# wm8731adapter.net
KiCad netlist of a schematic drawn in EAGLE
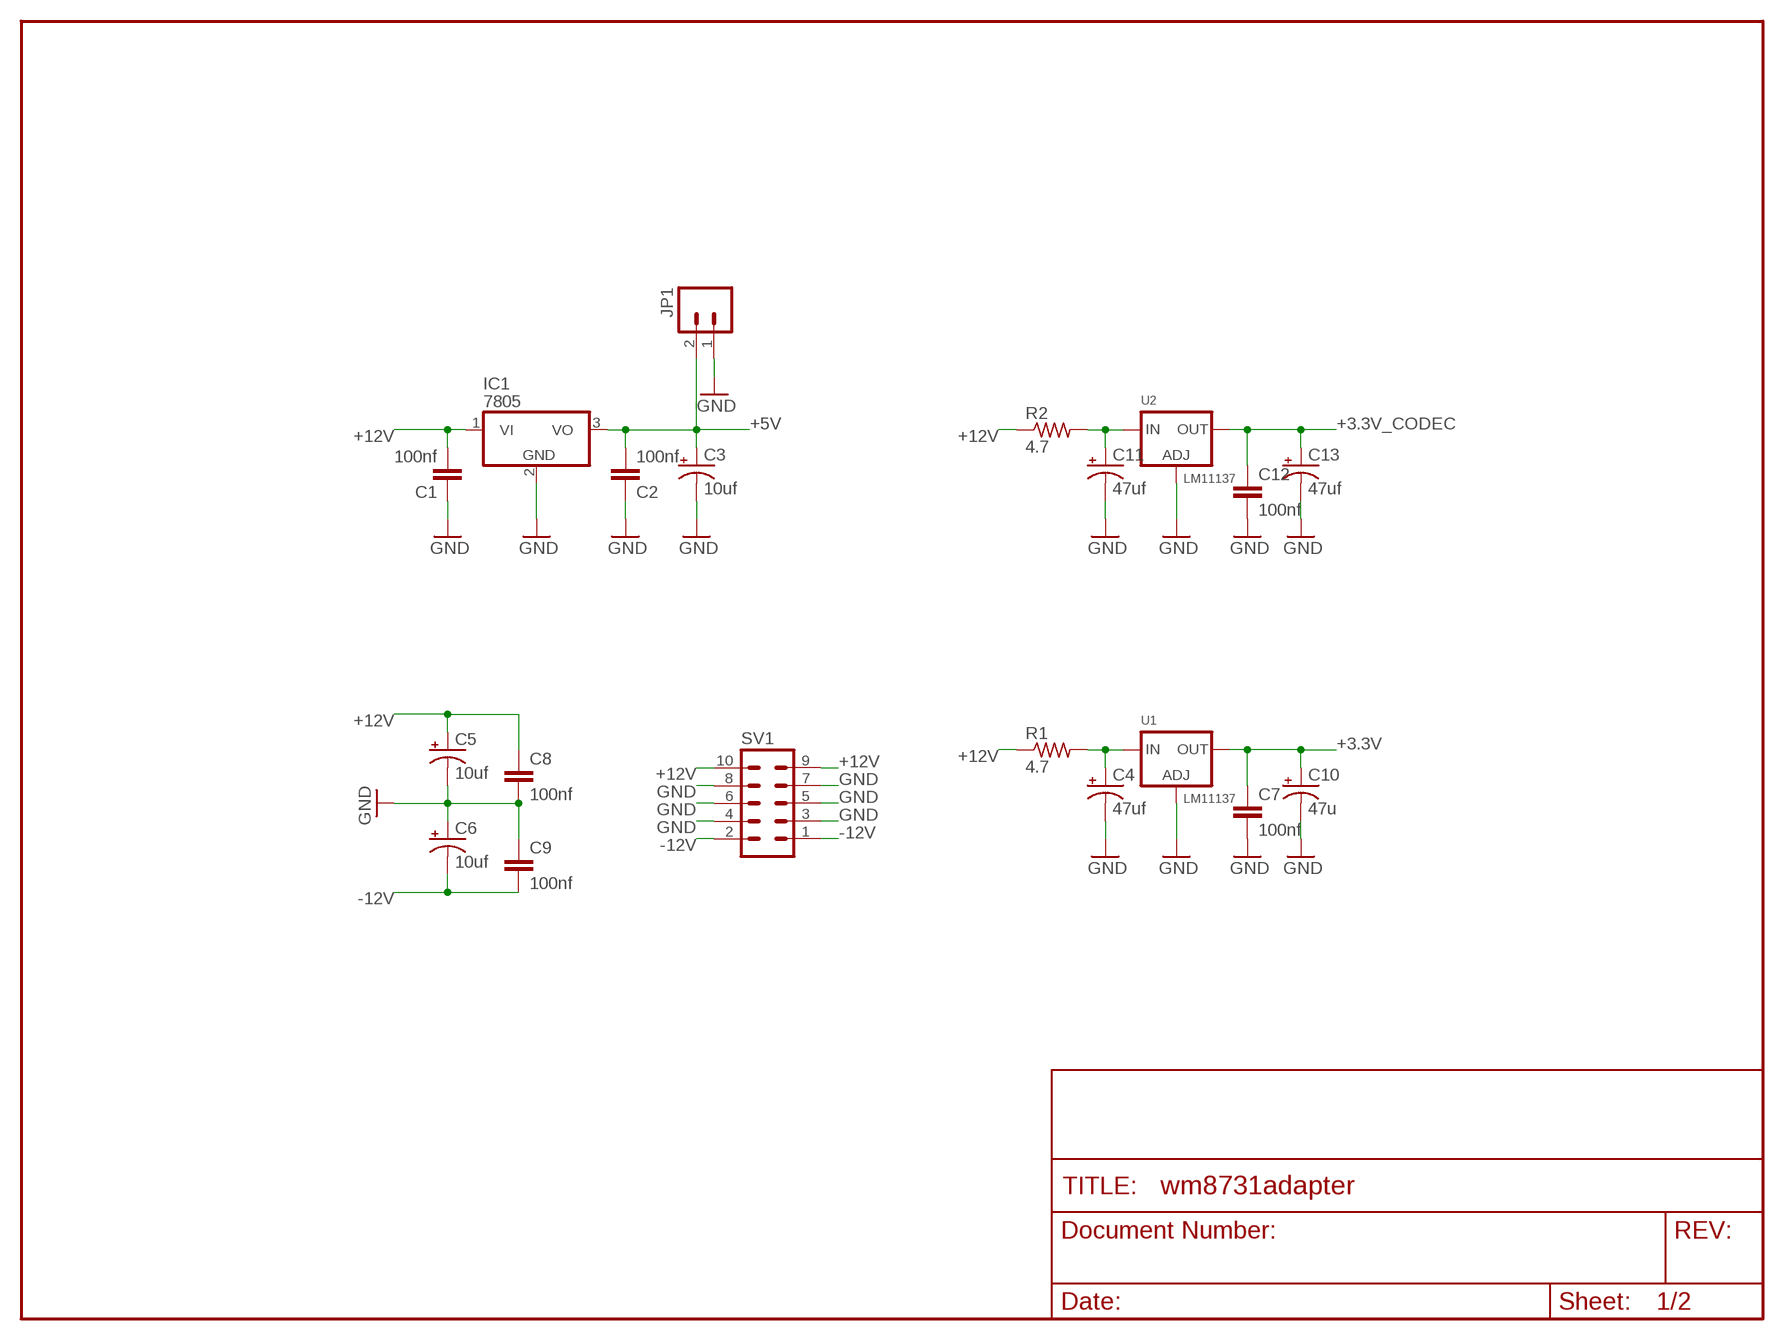
[diagram p0: schematic, sheet 1]
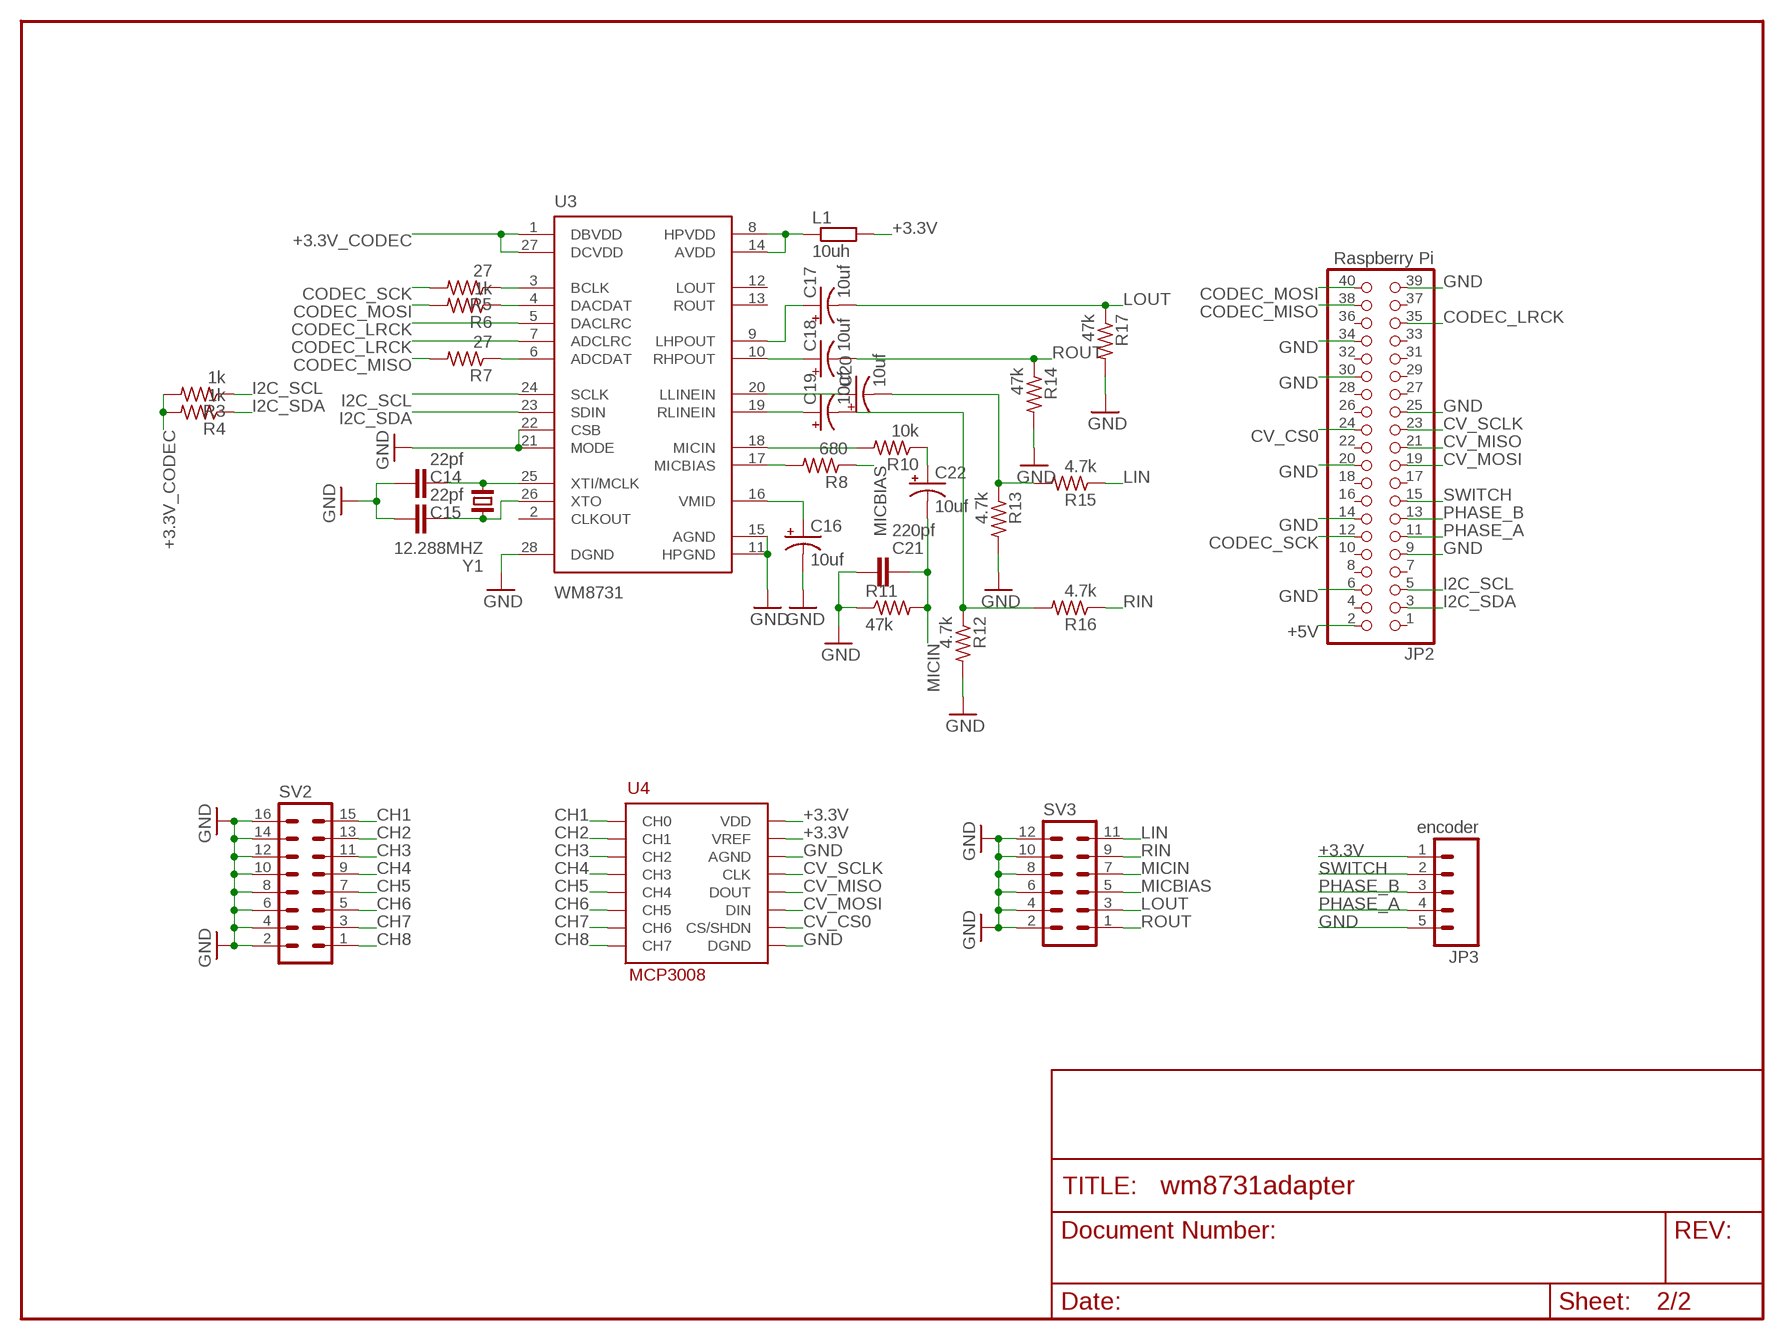
[diagram p1: schematic, sheet 2]

(export (version "E")
  (design (tool "Eeschema 10.0.6"))
  (components
    (comp (ref "C1")
      (value "100nf")
      (footprint "eagle-import:C0603")
      (libsource (lib "eagle-import") (part "C-EUC0603"))
    )
    (comp (ref "C2")
      (value "100nf")
      (footprint "eagle-import:C0603")
      (libsource (lib "eagle-import") (part "C-EUC0603"))
    )
    (comp (ref "C3")
      (value "10uf")
      (footprint "eagle-import:PANASONIC_C")
      (libsource (lib "eagle-import") (part "CPOL-USC"))
    )
    (comp (ref "C4")
      (value "47uf")
      (footprint "eagle-import:PANASONIC_D")
      (libsource (lib "eagle-import") (part "CPOL-USD"))
    )
    (comp (ref "C5")
      (value "10uf")
      (footprint "eagle-import:PANASONIC_C")
      (libsource (lib "eagle-import") (part "CPOL-USC"))
    )
    (comp (ref "C6")
      (value "10uf")
      (footprint "eagle-import:PANASONIC_C")
      (libsource (lib "eagle-import") (part "CPOL-USC"))
    )
    (comp (ref "C7")
      (value "100nf")
      (footprint "eagle-import:C0603")
      (libsource (lib "eagle-import") (part "C-EUC0603"))
    )
    (comp (ref "C8")
      (value "100nf")
      (footprint "eagle-import:C0603")
      (libsource (lib "eagle-import") (part "C-EUC0603"))
    )
    (comp (ref "C9")
      (value "100nf")
      (footprint "eagle-import:C0603")
      (libsource (lib "eagle-import") (part "C-EUC0603"))
    )
    (comp (ref "C10")
      (value "47u")
      (footprint "eagle-import:PANASONIC_D")
      (libsource (lib "eagle-import") (part "CPOL-USD"))
    )
    (comp (ref "C11")
      (value "47uf")
      (footprint "eagle-import:PANASONIC_D")
      (libsource (lib "eagle-import") (part "CPOL-USD"))
    )
    (comp (ref "C12")
      (value "100nf")
      (footprint "eagle-import:C0603")
      (libsource (lib "eagle-import") (part "C-EUC0603"))
    )
    (comp (ref "C13")
      (value "47uf")
      (footprint "eagle-import:PANASONIC_D")
      (libsource (lib "eagle-import") (part "CPOL-USD"))
    )
    (comp (ref "IC1")
      (value "7805")
      (footprint "eagle-import:TO220V")
      (libsource (lib "eagle-import") (part "78TV05"))
    )
    (comp (ref "JP1")
      (value "M02_HEADERPOLAR")
      (footprint "eagle-import:MOLEX-1X2")
      (libsource (lib "eagle-import") (part "M02_HEADERPOLAR"))
    )
    (comp (ref "R1")
      (value "4.7")
      (footprint "eagle-import:R1206")
      (libsource (lib "eagle-import") (part "R-US_R1206"))
    )
    (comp (ref "R2")
      (value "4.7")
      (footprint "eagle-import:R1206")
      (libsource (lib "eagle-import") (part "R-US_R1206"))
    )
    (comp (ref "SV1")
      (value "MA05-2")
      (footprint "eagle-import:MA05-2")
      (libsource (lib "eagle-import") (part "MA05-2"))
    )
    (comp (ref "U1")
      (value "LM11137")
      (footprint "eagle-import:TO252")
      (libsource (lib "eagle-import") (part "LM1117TO252"))
    )
    (comp (ref "U2")
      (value "LM11137")
      (footprint "eagle-import:SOT223-R")
      (libsource (lib "eagle-import") (part "LM1117SOT223-REFLOW"))
    )
    (comp (ref "C14")
      (value "22pf")
      (footprint "eagle-import:C0603")
      (libsource (lib "eagle-import") (part "C-EUC0603"))
    )
    (comp (ref "C15")
      (value "22pf")
      (footprint "eagle-import:C0603")
      (libsource (lib "eagle-import") (part "C-EUC0603"))
    )
    (comp (ref "C16")
      (value "10uf")
      (footprint "eagle-import:PANASONIC_C")
      (libsource (lib "eagle-import") (part "CPOL-USC"))
    )
    (comp (ref "C17")
      (value "10uf")
      (footprint "eagle-import:PANASONIC_C")
      (libsource (lib "eagle-import") (part "CPOL-USC"))
    )
    (comp (ref "C18")
      (value "10uf")
      (footprint "eagle-import:PANASONIC_C")
      (libsource (lib "eagle-import") (part "CPOL-USC"))
    )
    (comp (ref "C19")
      (value "10uf")
      (footprint "eagle-import:PANASONIC_C")
      (libsource (lib "eagle-import") (part "CPOL-USC"))
    )
    (comp (ref "C20")
      (value "10uf")
      (footprint "eagle-import:PANASONIC_C")
      (libsource (lib "eagle-import") (part "CPOL-USC"))
    )
    (comp (ref "C21")
      (value "220pf")
      (footprint "eagle-import:C0603")
      (libsource (lib "eagle-import") (part "C-EUC0603"))
    )
    (comp (ref "C22")
      (value "10uf")
      (footprint "eagle-import:PANASONIC_C")
      (libsource (lib "eagle-import") (part "CPOL-USC"))
    )
    (comp (ref "JP2")
      (value "Raspberry Pi")
      (footprint "eagle-import:2X20")
      (libsource (lib "eagle-import") (part "PINHD-2X20"))
    )
    (comp (ref "JP3")
      (value "encoder")
      (footprint "eagle-import:1X05")
      (libsource (lib "eagle-import") (part "M05PTH"))
    )
    (comp (ref "L1")
      (value "10uh")
      (footprint "eagle-import:1_4W_RESISTOR")
      (libsource (lib "eagle-import") (part "RESISTOR10MM"))
    )
    (comp (ref "R3")
      (value "1k")
      (footprint "eagle-import:R0603")
      (libsource (lib "eagle-import") (part "R-US_R0603"))
    )
    (comp (ref "R4")
      (value "1k")
      (footprint "eagle-import:R0603")
      (libsource (lib "eagle-import") (part "R-US_R0603"))
    )
    (comp (ref "R5")
      (value "27")
      (footprint "eagle-import:R0603")
      (libsource (lib "eagle-import") (part "R-US_R0603"))
    )
    (comp (ref "R6")
      (value "1k")
      (footprint "eagle-import:R0603")
      (libsource (lib "eagle-import") (part "R-US_R0603"))
    )
    (comp (ref "R7")
      (value "27")
      (footprint "eagle-import:R0603")
      (libsource (lib "eagle-import") (part "R-US_R0603"))
    )
    (comp (ref "R8")
      (value "680")
      (footprint "eagle-import:R0603")
      (libsource (lib "eagle-import") (part "R-US_R0603"))
    )
    (comp (ref "R10")
      (value "10k")
      (footprint "eagle-import:R0603")
      (libsource (lib "eagle-import") (part "R-US_R0603"))
    )
    (comp (ref "R11")
      (value "47k")
      (footprint "eagle-import:R0603")
      (libsource (lib "eagle-import") (part "R-US_R0603"))
    )
    (comp (ref "R12")
      (value "4.7k")
      (footprint "eagle-import:R0603")
      (libsource (lib "eagle-import") (part "R-US_R0603"))
    )
    (comp (ref "R13")
      (value "4.7k")
      (footprint "eagle-import:R0603")
      (libsource (lib "eagle-import") (part "R-US_R0603"))
    )
    (comp (ref "R14")
      (value "47k")
      (footprint "eagle-import:R0603")
      (libsource (lib "eagle-import") (part "R-US_R0603"))
    )
    (comp (ref "R15")
      (value "4.7k")
      (footprint "eagle-import:R0603")
      (libsource (lib "eagle-import") (part "R-US_R0603"))
    )
    (comp (ref "R16")
      (value "4.7k")
      (footprint "eagle-import:R0603")
      (libsource (lib "eagle-import") (part "R-US_R0603"))
    )
    (comp (ref "R17")
      (value "47k")
      (footprint "eagle-import:R0603")
      (libsource (lib "eagle-import") (part "R-US_R0603"))
    )
    (comp (ref "SV2")
      (value "MA08-2")
      (footprint "eagle-import:MA08-2")
      (libsource (lib "eagle-import") (part "MA08-2"))
    )
    (comp (ref "SV3")
      (value "MA06-2")
      (footprint "eagle-import:MA06-2")
      (libsource (lib "eagle-import") (part "MA06-2"))
    )
    (comp (ref "U3")
      (value "WM8731")
      (footprint "eagle-import:SSOP28")
      (libsource (lib "eagle-import") (part "WM8731"))
    )
    (comp (ref "U4")
      (value "MCP3008")
      (footprint "eagle-import:SOIC16")
      (libsource (lib "eagle-import") (part "MCP3008"))
    )
    (comp (ref "Y1")
      (value "12.288MHZ")
      (footprint "eagle-import:HC49UP")
      (libsource (lib "eagle-import") (part "CRYTALHCM49"))
    )
  )
  (nets
    (net (code "1") (name "+3.3V") (class "Default")
      (node (ref "C10") (pin "+") (pinfunction "+_+") (pintype "passive"))
      (node (ref "C7") (pin "1") (pinfunction "1_1") (pintype "passive"))
      (node (ref "JP3") (pin "1") (pinfunction "1_1") (pintype "passive"))
      (node (ref "L1") (pin "2") (pinfunction "2_2") (pintype "passive"))
      (node (ref "U1") (pin "3") (pinfunction "OUT_3") (pintype "passive"))
      (node (ref "U4") (pin "15") (pinfunction "VREF_15") (pintype "bidirectional"))
      (node (ref "U4") (pin "16") (pinfunction "VDD_16") (pintype "bidirectional"))
    )
    (net (code "2") (name "+3.3V_CODEC") (class "Default")
      (node (ref "C12") (pin "1") (pinfunction "1_1") (pintype "passive"))
      (node (ref "C13") (pin "+") (pinfunction "+_+") (pintype "passive"))
      (node (ref "R3") (pin "2") (pinfunction "2_2") (pintype "passive"))
      (node (ref "R4") (pin "2") (pinfunction "2_2") (pintype "passive"))
      (node (ref "U2") (pin "2") (pinfunction "OUT_2") (pintype "passive"))
      (node (ref "U3") (pin "1") (pinfunction "DBVDD_1") (pintype "bidirectional"))
      (node (ref "U3") (pin "27") (pinfunction "DCVDD_27") (pintype "bidirectional"))
    )
    (net (code "3") (name "+5V") (class "Default")
      (node (ref "C2") (pin "2") (pinfunction "2_2") (pintype "passive"))
      (node (ref "C3") (pin "+") (pinfunction "+_+") (pintype "passive"))
      (node (ref "IC1") (pin "3") (pinfunction "VO_3") (pintype "passive"))
      (node (ref "JP1") (pin "2") (pinfunction "2_2") (pintype "passive"))
      (node (ref "JP2") (pin "2") (pinfunction "2_2") (pintype "passive"))
    )
    (net (code "4") (name "+12V") (class "Default")
      (node (ref "C1") (pin "2") (pinfunction "2_2") (pintype "passive"))
      (node (ref "C5") (pin "+") (pinfunction "+_+") (pintype "passive"))
      (node (ref "C8") (pin "1") (pinfunction "1_1") (pintype "passive"))
      (node (ref "IC1") (pin "1") (pinfunction "VI_1") (pintype "input"))
      (node (ref "R1") (pin "1") (pinfunction "1_1") (pintype "passive"))
      (node (ref "R2") (pin "1") (pinfunction "1_1") (pintype "passive"))
      (node (ref "SV1") (pin "10") (pinfunction "10_10") (pintype "passive"))
      (node (ref "SV1") (pin "9") (pinfunction "9_9") (pintype "passive"))
    )
    (net (code "5") (name "-12V") (class "Default")
      (node (ref "C6") (pin "-") (pinfunction "-_-") (pintype "passive"))
      (node (ref "C9") (pin "2") (pinfunction "2_2") (pintype "passive"))
      (node (ref "SV1") (pin "1") (pinfunction "1_1") (pintype "passive"))
      (node (ref "SV1") (pin "2") (pinfunction "2_2") (pintype "passive"))
    )
    (net (code "6") (name "CH1") (class "Default")
      (node (ref "SV2") (pin "15") (pinfunction "15_15") (pintype "passive"))
      (node (ref "U4") (pin "1") (pinfunction "CH0_1") (pintype "bidirectional"))
    )
    (net (code "7") (name "CH2") (class "Default")
      (node (ref "SV2") (pin "13") (pinfunction "13_13") (pintype "passive"))
      (node (ref "U4") (pin "2") (pinfunction "CH1_2") (pintype "bidirectional"))
    )
    (net (code "8") (name "CH3") (class "Default")
      (node (ref "SV2") (pin "11") (pinfunction "11_11") (pintype "passive"))
      (node (ref "U4") (pin "3") (pinfunction "CH2_3") (pintype "bidirectional"))
    )
    (net (code "9") (name "CH4") (class "Default")
      (node (ref "SV2") (pin "9") (pinfunction "9_9") (pintype "passive"))
      (node (ref "U4") (pin "4") (pinfunction "CH3_4") (pintype "bidirectional"))
    )
    (net (code "10") (name "CH5") (class "Default")
      (node (ref "SV2") (pin "7") (pinfunction "7_7") (pintype "passive"))
      (node (ref "U4") (pin "5") (pinfunction "CH4_5") (pintype "bidirectional"))
    )
    (net (code "11") (name "CH6") (class "Default")
      (node (ref "SV2") (pin "5") (pinfunction "5_5") (pintype "passive"))
      (node (ref "U4") (pin "6") (pinfunction "CH5_6") (pintype "bidirectional"))
    )
    (net (code "12") (name "CH7") (class "Default")
      (node (ref "SV2") (pin "3") (pinfunction "3_3") (pintype "passive"))
      (node (ref "U4") (pin "7") (pinfunction "CH6_7") (pintype "bidirectional"))
    )
    (net (code "13") (name "CH8") (class "Default")
      (node (ref "SV2") (pin "1") (pinfunction "1_1") (pintype "passive"))
      (node (ref "U4") (pin "8") (pinfunction "CH7_8") (pintype "bidirectional"))
    )
    (net (code "14") (name "CODEC_LRCK") (class "Default")
      (node (ref "JP2") (pin "35") (pinfunction "35_35") (pintype "passive"))
      (node (ref "U3") (pin "5") (pinfunction "DACLRC_5") (pintype "bidirectional"))
      (node (ref "U3") (pin "7") (pinfunction "ADCLRC_7") (pintype "bidirectional"))
    )
    (net (code "15") (name "CODEC_MISO") (class "Default")
      (node (ref "JP2") (pin "38") (pinfunction "38_38") (pintype "passive"))
      (node (ref "R7") (pin "2") (pinfunction "2_2") (pintype "passive"))
    )
    (net (code "16") (name "CODEC_MOSI") (class "Default")
      (node (ref "JP2") (pin "40") (pinfunction "40_40") (pintype "passive"))
      (node (ref "R6") (pin "2") (pinfunction "2_2") (pintype "passive"))
    )
    (net (code "17") (name "CODEC_SCK") (class "Default")
      (node (ref "JP2") (pin "12") (pinfunction "12_12") (pintype "passive"))
      (node (ref "R5") (pin "2") (pinfunction "2_2") (pintype "passive"))
    )
    (net (code "18") (name "CV_CS0") (class "Default")
      (node (ref "JP2") (pin "24") (pinfunction "24_24") (pintype "passive"))
      (node (ref "U4") (pin "10") (pinfunction "CS/SHDN_10") (pintype "bidirectional"))
    )
    (net (code "19") (name "CV_MISO") (class "Default")
      (node (ref "JP2") (pin "21") (pinfunction "21_21") (pintype "passive"))
      (node (ref "U4") (pin "12") (pinfunction "DOUT_12") (pintype "bidirectional"))
    )
    (net (code "20") (name "CV_MOSI") (class "Default")
      (node (ref "JP2") (pin "19") (pinfunction "19_19") (pintype "passive"))
      (node (ref "U4") (pin "11") (pinfunction "DIN_11") (pintype "bidirectional"))
    )
    (net (code "21") (name "CV_SCLK") (class "Default")
      (node (ref "JP2") (pin "23") (pinfunction "23_23") (pintype "passive"))
      (node (ref "U4") (pin "13") (pinfunction "CLK_13") (pintype "bidirectional"))
    )
    (net (code "22") (name "GND") (class "Default")
      (node (ref "C1") (pin "1") (pinfunction "1_1") (pintype "passive"))
      (node (ref "C10") (pin "-") (pinfunction "-_-") (pintype "passive"))
      (node (ref "C11") (pin "-") (pinfunction "-_-") (pintype "passive"))
      (node (ref "C12") (pin "2") (pinfunction "2_2") (pintype "passive"))
      (node (ref "C13") (pin "-") (pinfunction "-_-") (pintype "passive"))
      (node (ref "C14") (pin "2") (pinfunction "2_2") (pintype "passive"))
      (node (ref "C15") (pin "2") (pinfunction "2_2") (pintype "passive"))
      (node (ref "C16") (pin "-") (pinfunction "-_-") (pintype "passive"))
      (node (ref "C2") (pin "1") (pinfunction "1_1") (pintype "passive"))
      (node (ref "C21") (pin "1") (pinfunction "1_1") (pintype "passive"))
      (node (ref "C3") (pin "-") (pinfunction "-_-") (pintype "passive"))
      (node (ref "C4") (pin "-") (pinfunction "-_-") (pintype "passive"))
      (node (ref "C5") (pin "-") (pinfunction "-_-") (pintype "passive"))
      (node (ref "C6") (pin "+") (pinfunction "+_+") (pintype "passive"))
      (node (ref "C7") (pin "2") (pinfunction "2_2") (pintype "passive"))
      (node (ref "C8") (pin "2") (pinfunction "2_2") (pintype "passive"))
      (node (ref "C9") (pin "1") (pinfunction "1_1") (pintype "passive"))
      (node (ref "IC1") (pin "2") (pinfunction "GND_2") (pintype "passive"))
      (node (ref "JP1") (pin "1") (pinfunction "1_1") (pintype "passive"))
      (node (ref "JP2") (pin "14") (pinfunction "14_14") (pintype "passive"))
      (node (ref "JP2") (pin "20") (pinfunction "20_20") (pintype "passive"))
      (node (ref "JP2") (pin "25") (pinfunction "25_25") (pintype "passive"))
      (node (ref "JP2") (pin "30") (pinfunction "30_30") (pintype "passive"))
      (node (ref "JP2") (pin "34") (pinfunction "34_34") (pintype "passive"))
      (node (ref "JP2") (pin "39") (pinfunction "39_39") (pintype "passive"))
      (node (ref "JP2") (pin "6") (pinfunction "6_6") (pintype "passive"))
      (node (ref "JP2") (pin "9") (pinfunction "9_9") (pintype "passive"))
      (node (ref "JP3") (pin "5") (pinfunction "5_5") (pintype "passive"))
      (node (ref "R11") (pin "1") (pinfunction "1_1") (pintype "passive"))
      (node (ref "R12") (pin "2") (pinfunction "2_2") (pintype "passive"))
      (node (ref "R13") (pin "2") (pinfunction "2_2") (pintype "passive"))
      (node (ref "R14") (pin "2") (pinfunction "2_2") (pintype "passive"))
      (node (ref "R17") (pin "2") (pinfunction "2_2") (pintype "passive"))
      (node (ref "SV1") (pin "3") (pinfunction "3_3") (pintype "passive"))
      (node (ref "SV1") (pin "4") (pinfunction "4_4") (pintype "passive"))
      (node (ref "SV1") (pin "5") (pinfunction "5_5") (pintype "passive"))
      (node (ref "SV1") (pin "6") (pinfunction "6_6") (pintype "passive"))
      (node (ref "SV1") (pin "7") (pinfunction "7_7") (pintype "passive"))
      (node (ref "SV1") (pin "8") (pinfunction "8_8") (pintype "passive"))
      (node (ref "SV2") (pin "10") (pinfunction "10_10") (pintype "passive"))
      (node (ref "SV2") (pin "12") (pinfunction "12_12") (pintype "passive"))
      (node (ref "SV2") (pin "14") (pinfunction "14_14") (pintype "passive"))
      (node (ref "SV2") (pin "16") (pinfunction "16_16") (pintype "passive"))
      (node (ref "SV2") (pin "2") (pinfunction "2_2") (pintype "passive"))
      (node (ref "SV2") (pin "4") (pinfunction "4_4") (pintype "passive"))
      (node (ref "SV2") (pin "6") (pinfunction "6_6") (pintype "passive"))
      (node (ref "SV2") (pin "8") (pinfunction "8_8") (pintype "passive"))
      (node (ref "SV3") (pin "10") (pinfunction "10_10") (pintype "passive"))
      (node (ref "SV3") (pin "12") (pinfunction "12_12") (pintype "passive"))
      (node (ref "SV3") (pin "2") (pinfunction "2_2") (pintype "passive"))
      (node (ref "SV3") (pin "4") (pinfunction "4_4") (pintype "passive"))
      (node (ref "SV3") (pin "6") (pinfunction "6_6") (pintype "passive"))
      (node (ref "SV3") (pin "8") (pinfunction "8_8") (pintype "passive"))
      (node (ref "U1") (pin "1") (pinfunction "ADJ_1") (pintype "input"))
      (node (ref "U2") (pin "1") (pinfunction "ADJ_1") (pintype "input"))
      (node (ref "U3") (pin "11") (pinfunction "HPGND_11") (pintype "bidirectional"))
      (node (ref "U3") (pin "15") (pinfunction "AGND_15") (pintype "bidirectional"))
      (node (ref "U3") (pin "21") (pinfunction "MODE_21") (pintype "bidirectional"))
      (node (ref "U3") (pin "22") (pinfunction "CSB_22") (pintype "bidirectional"))
      (node (ref "U3") (pin "28") (pinfunction "DGND_28") (pintype "bidirectional"))
      (node (ref "U4") (pin "14") (pinfunction "AGND_14") (pintype "bidirectional"))
      (node (ref "U4") (pin "9") (pinfunction "DGND_9") (pintype "bidirectional"))
    )
    (net (code "23") (name "I2C_SCL") (class "Default")
      (node (ref "JP2") (pin "5") (pinfunction "5_5") (pintype "passive"))
      (node (ref "R3") (pin "1") (pinfunction "1_1") (pintype "passive"))
      (node (ref "U3") (pin "24") (pinfunction "SCLK_24") (pintype "bidirectional"))
    )
    (net (code "24") (name "I2C_SDA") (class "Default")
      (node (ref "JP2") (pin "3") (pinfunction "3_3") (pintype "passive"))
      (node (ref "R4") (pin "1") (pinfunction "1_1") (pintype "passive"))
      (node (ref "U3") (pin "23") (pinfunction "SDIN_23") (pintype "bidirectional"))
    )
    (net (code "25") (name "LIN") (class "Default")
      (node (ref "R15") (pin "1") (pinfunction "1_1") (pintype "passive"))
      (node (ref "SV3") (pin "11") (pinfunction "11_11") (pintype "passive"))
    )
    (net (code "26") (name "LOUT") (class "Default")
      (node (ref "C17") (pin "-") (pinfunction "-_-") (pintype "passive"))
      (node (ref "R17") (pin "1") (pinfunction "1_1") (pintype "passive"))
      (node (ref "SV3") (pin "3") (pinfunction "3_3") (pintype "passive"))
    )
    (net (code "27") (name "MICBIAS") (class "Default")
      (node (ref "R8") (pin "1") (pinfunction "1_1") (pintype "passive"))
      (node (ref "SV3") (pin "5") (pinfunction "5_5") (pintype "passive"))
    )
    (net (code "28") (name "MICIN") (class "Default")
      (node (ref "C21") (pin "2") (pinfunction "2_2") (pintype "passive"))
      (node (ref "C22") (pin "-") (pinfunction "-_-") (pintype "passive"))
      (node (ref "R11") (pin "2") (pinfunction "2_2") (pintype "passive"))
      (node (ref "SV3") (pin "7") (pinfunction "7_7") (pintype "passive"))
    )
    (net (code "29") (name "Net-(C19-Pad-)") (class "Default")
      (node (ref "C19") (pin "-") (pinfunction "-_-") (pintype "passive"))
      (node (ref "R12") (pin "1") (pinfunction "1_1") (pintype "passive"))
      (node (ref "R16") (pin "2") (pinfunction "2_2") (pintype "passive"))
    )
    (net (code "30") (name "Net-(C20-Pad-)") (class "Default")
      (node (ref "C20") (pin "-") (pinfunction "-_-") (pintype "passive"))
      (node (ref "R13") (pin "1") (pinfunction "1_1") (pintype "passive"))
      (node (ref "R15") (pin "2") (pinfunction "2_2") (pintype "passive"))
    )
    (net (code "31") (name "Net-(C22-Pad+)") (class "Default")
      (node (ref "C22") (pin "+") (pinfunction "+_+") (pintype "passive"))
      (node (ref "R10") (pin "1") (pinfunction "1_1") (pintype "passive"))
    )
    (net (code "32") (name "Net-(U1-IN)") (class "Default")
      (node (ref "C4") (pin "+") (pinfunction "+_+") (pintype "passive"))
      (node (ref "R1") (pin "2") (pinfunction "2_2") (pintype "passive"))
      (node (ref "U1") (pin "2") (pinfunction "IN_2") (pintype "input"))
    )
    (net (code "33") (name "Net-(U2-IN)") (class "Default")
      (node (ref "C11") (pin "+") (pinfunction "+_+") (pintype "passive"))
      (node (ref "R2") (pin "2") (pinfunction "2_2") (pintype "passive"))
      (node (ref "U2") (pin "3") (pinfunction "IN_3") (pintype "input"))
    )
    (net (code "34") (name "Net-(U3-ADCDAT)") (class "Default")
      (node (ref "R7") (pin "1") (pinfunction "1_1") (pintype "passive"))
      (node (ref "U3") (pin "6") (pinfunction "ADCDAT_6") (pintype "bidirectional"))
    )
    (net (code "35") (name "Net-(U3-AVDD)") (class "Default")
      (node (ref "L1") (pin "1") (pinfunction "1_1") (pintype "passive"))
      (node (ref "U3") (pin "14") (pinfunction "AVDD_14") (pintype "bidirectional"))
      (node (ref "U3") (pin "8") (pinfunction "HPVDD_8") (pintype "bidirectional"))
    )
    (net (code "36") (name "Net-(U3-BCLK)") (class "Default")
      (node (ref "R5") (pin "1") (pinfunction "1_1") (pintype "passive"))
      (node (ref "U3") (pin "3") (pinfunction "BCLK_3") (pintype "bidirectional"))
    )
    (net (code "37") (name "Net-(U3-DACDAT)") (class "Default")
      (node (ref "R6") (pin "1") (pinfunction "1_1") (pintype "passive"))
      (node (ref "U3") (pin "4") (pinfunction "DACDAT_4") (pintype "bidirectional"))
    )
    (net (code "38") (name "Net-(U3-LHPOUT)") (class "Default")
      (node (ref "C17") (pin "+") (pinfunction "+_+") (pintype "passive"))
      (node (ref "U3") (pin "9") (pinfunction "LHPOUT_9") (pintype "bidirectional"))
    )
    (net (code "39") (name "Net-(U3-LLINEIN)") (class "Default")
      (node (ref "C20") (pin "+") (pinfunction "+_+") (pintype "passive"))
      (node (ref "U3") (pin "20") (pinfunction "LLINEIN_20") (pintype "bidirectional"))
    )
    (net (code "40") (name "Net-(U3-MICBIAS)") (class "Default")
      (node (ref "R8") (pin "2") (pinfunction "2_2") (pintype "passive"))
      (node (ref "U3") (pin "17") (pinfunction "MICBIAS_17") (pintype "bidirectional"))
    )
    (net (code "41") (name "Net-(U3-MICIN)") (class "Default")
      (node (ref "R10") (pin "2") (pinfunction "2_2") (pintype "passive"))
      (node (ref "U3") (pin "18") (pinfunction "MICIN_18") (pintype "bidirectional"))
    )
    (net (code "42") (name "Net-(U3-RHPOUT)") (class "Default")
      (node (ref "C18") (pin "+") (pinfunction "+_+") (pintype "passive"))
      (node (ref "U3") (pin "10") (pinfunction "RHPOUT_10") (pintype "bidirectional"))
    )
    (net (code "43") (name "Net-(U3-RLINEIN)") (class "Default")
      (node (ref "C19") (pin "+") (pinfunction "+_+") (pintype "passive"))
      (node (ref "U3") (pin "19") (pinfunction "RLINEIN_19") (pintype "bidirectional"))
    )
    (net (code "44") (name "Net-(U3-VMID)") (class "Default")
      (node (ref "C16") (pin "+") (pinfunction "+_+") (pintype "passive"))
      (node (ref "U3") (pin "16") (pinfunction "VMID_16") (pintype "bidirectional"))
    )
    (net (code "45") (name "Net-(U3-XTI{slash}MCLK)") (class "Default")
      (node (ref "C14") (pin "1") (pinfunction "1_1") (pintype "passive"))
      (node (ref "U3") (pin "25") (pinfunction "XTI/MCLK_25") (pintype "bidirectional"))
      (node (ref "Y1") (pin "2") (pinfunction "2_2") (pintype "passive"))
    )
    (net (code "46") (name "Net-(U3-XTO)") (class "Default")
      (node (ref "C15") (pin "1") (pinfunction "1_1") (pintype "passive"))
      (node (ref "U3") (pin "26") (pinfunction "XTO_26") (pintype "bidirectional"))
      (node (ref "Y1") (pin "1") (pinfunction "1_1") (pintype "passive"))
    )
    (net (code "47") (name "PHASE_A") (class "Default")
      (node (ref "JP2") (pin "11") (pinfunction "11_11") (pintype "passive"))
      (node (ref "JP3") (pin "4") (pinfunction "4_4") (pintype "passive"))
    )
    (net (code "48") (name "PHASE_B") (class "Default")
      (node (ref "JP2") (pin "13") (pinfunction "13_13") (pintype "passive"))
      (node (ref "JP3") (pin "3") (pinfunction "3_3") (pintype "passive"))
    )
    (net (code "49") (name "RIN") (class "Default")
      (node (ref "R16") (pin "1") (pinfunction "1_1") (pintype "passive"))
      (node (ref "SV3") (pin "9") (pinfunction "9_9") (pintype "passive"))
    )
    (net (code "50") (name "ROUT") (class "Default")
      (node (ref "C18") (pin "-") (pinfunction "-_-") (pintype "passive"))
      (node (ref "R14") (pin "1") (pinfunction "1_1") (pintype "passive"))
      (node (ref "SV3") (pin "1") (pinfunction "1_1") (pintype "passive"))
    )
    (net (code "51") (name "SWITCH") (class "Default")
      (node (ref "JP2") (pin "15") (pinfunction "15_15") (pintype "passive"))
      (node (ref "JP3") (pin "2") (pinfunction "2_2") (pintype "passive"))
    )
    (net (code "52") (name "unconnected-(JP2-Pad1)") (class "Default")
      (node (ref "JP2") (pin "1") (pinfunction "1_1") (pintype "passive"))
    )
    (net (code "53") (name "unconnected-(JP2-Pad4)") (class "Default")
      (node (ref "JP2") (pin "4") (pinfunction "4_4") (pintype "passive"))
    )
    (net (code "54") (name "unconnected-(JP2-Pad7)") (class "Default")
      (node (ref "JP2") (pin "7") (pinfunction "7_7") (pintype "passive"))
    )
    (net (code "55") (name "unconnected-(JP2-Pad8)") (class "Default")
      (node (ref "JP2") (pin "8") (pinfunction "8_8") (pintype "passive"))
    )
    (net (code "56") (name "unconnected-(JP2-Pad10)") (class "Default")
      (node (ref "JP2") (pin "10") (pinfunction "10_10") (pintype "passive"))
    )
    (net (code "57") (name "unconnected-(JP2-Pad16)") (class "Default")
      (node (ref "JP2") (pin "16") (pinfunction "16_16") (pintype "passive"))
    )
    (net (code "58") (name "unconnected-(JP2-Pad17)") (class "Default")
      (node (ref "JP2") (pin "17") (pinfunction "17_17") (pintype "passive"))
    )
    (net (code "59") (name "unconnected-(JP2-Pad18)") (class "Default")
      (node (ref "JP2") (pin "18") (pinfunction "18_18") (pintype "passive"))
    )
    (net (code "60") (name "unconnected-(JP2-Pad22)") (class "Default")
      (node (ref "JP2") (pin "22") (pinfunction "22_22") (pintype "passive"))
    )
    (net (code "61") (name "unconnected-(JP2-Pad26)") (class "Default")
      (node (ref "JP2") (pin "26") (pinfunction "26_26") (pintype "passive"))
    )
    (net (code "62") (name "unconnected-(JP2-Pad27)") (class "Default")
      (node (ref "JP2") (pin "27") (pinfunction "27_27") (pintype "passive"))
    )
    (net (code "63") (name "unconnected-(JP2-Pad28)") (class "Default")
      (node (ref "JP2") (pin "28") (pinfunction "28_28") (pintype "passive"))
    )
    (net (code "64") (name "unconnected-(JP2-Pad29)") (class "Default")
      (node (ref "JP2") (pin "29") (pinfunction "29_29") (pintype "passive"))
    )
    (net (code "65") (name "unconnected-(JP2-Pad31)") (class "Default")
      (node (ref "JP2") (pin "31") (pinfunction "31_31") (pintype "passive"))
    )
    (net (code "66") (name "unconnected-(JP2-Pad32)") (class "Default")
      (node (ref "JP2") (pin "32") (pinfunction "32_32") (pintype "passive"))
    )
    (net (code "67") (name "unconnected-(JP2-Pad33)") (class "Default")
      (node (ref "JP2") (pin "33") (pinfunction "33_33") (pintype "passive"))
    )
    (net (code "68") (name "unconnected-(JP2-Pad36)") (class "Default")
      (node (ref "JP2") (pin "36") (pinfunction "36_36") (pintype "passive"))
    )
    (net (code "69") (name "unconnected-(JP2-Pad37)") (class "Default")
      (node (ref "JP2") (pin "37") (pinfunction "37_37") (pintype "passive"))
    )
    (net (code "70") (name "unconnected-(U3-CLKOUT-Pad2)") (class "Default")
      (node (ref "U3") (pin "2") (pinfunction "CLKOUT_2") (pintype "bidirectional"))
    )
    (net (code "71") (name "unconnected-(U3-LOUT-Pad12)") (class "Default")
      (node (ref "U3") (pin "12") (pinfunction "LOUT_12") (pintype "bidirectional"))
    )
    (net (code "72") (name "unconnected-(U3-ROUT-Pad13)") (class "Default")
      (node (ref "U3") (pin "13") (pinfunction "ROUT_13") (pintype "bidirectional"))
    )
  )
)
